# IMD_Fixed.net
KiCad netlist of a schematic drawn in EAGLE
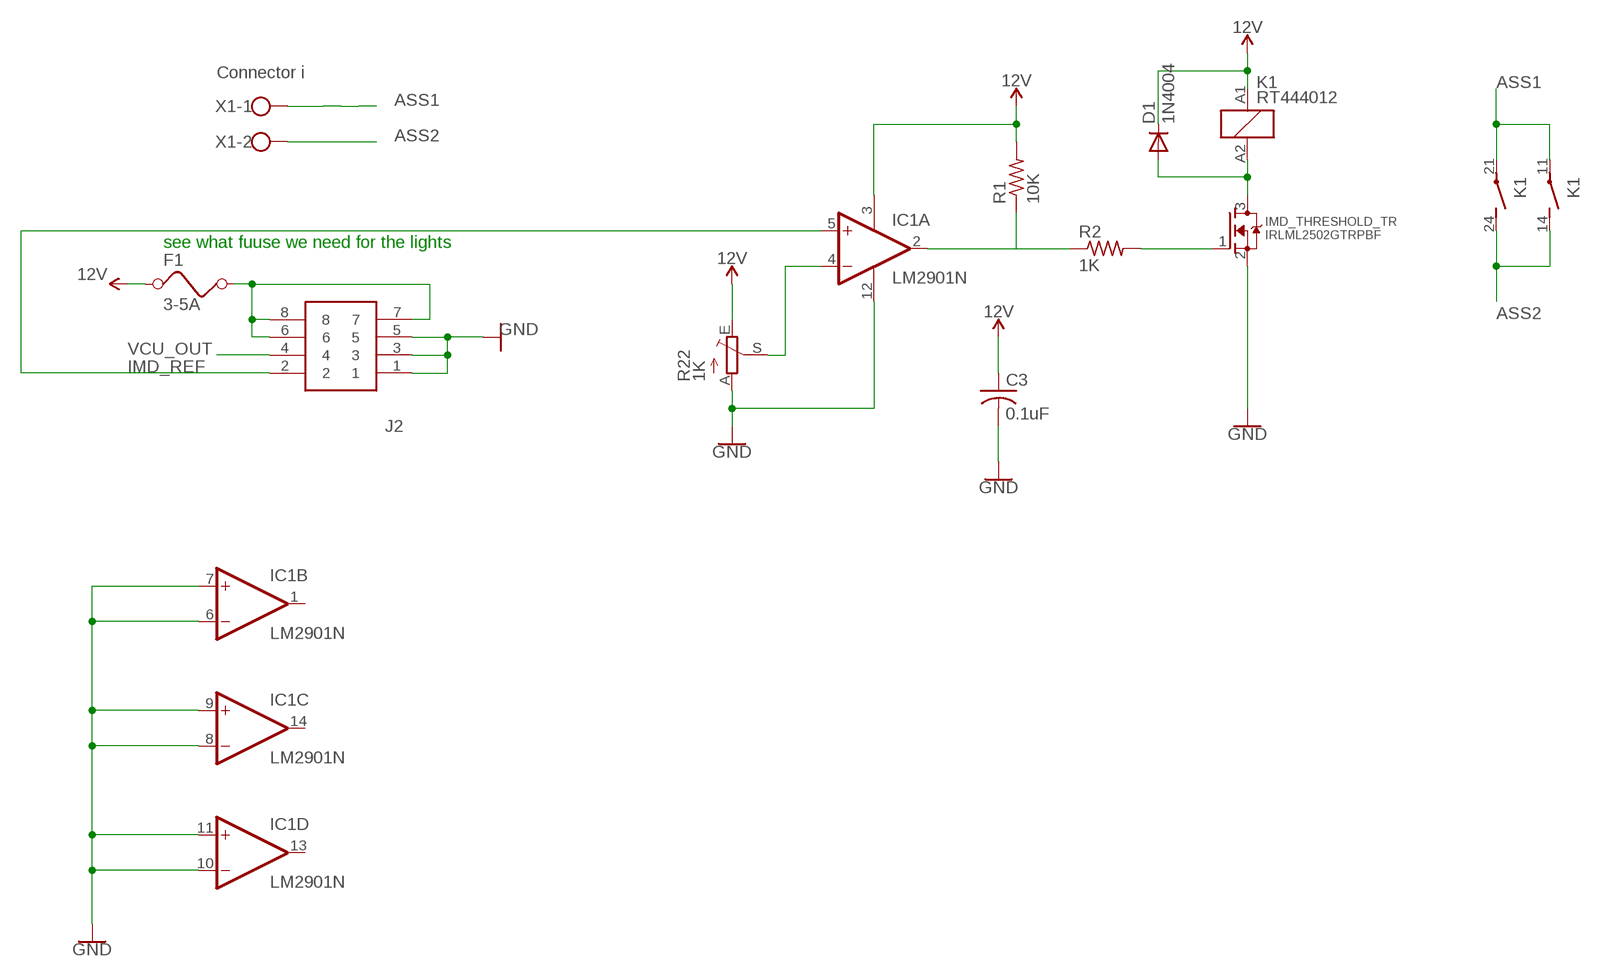
[diagram p0: schematic, sheet 1]
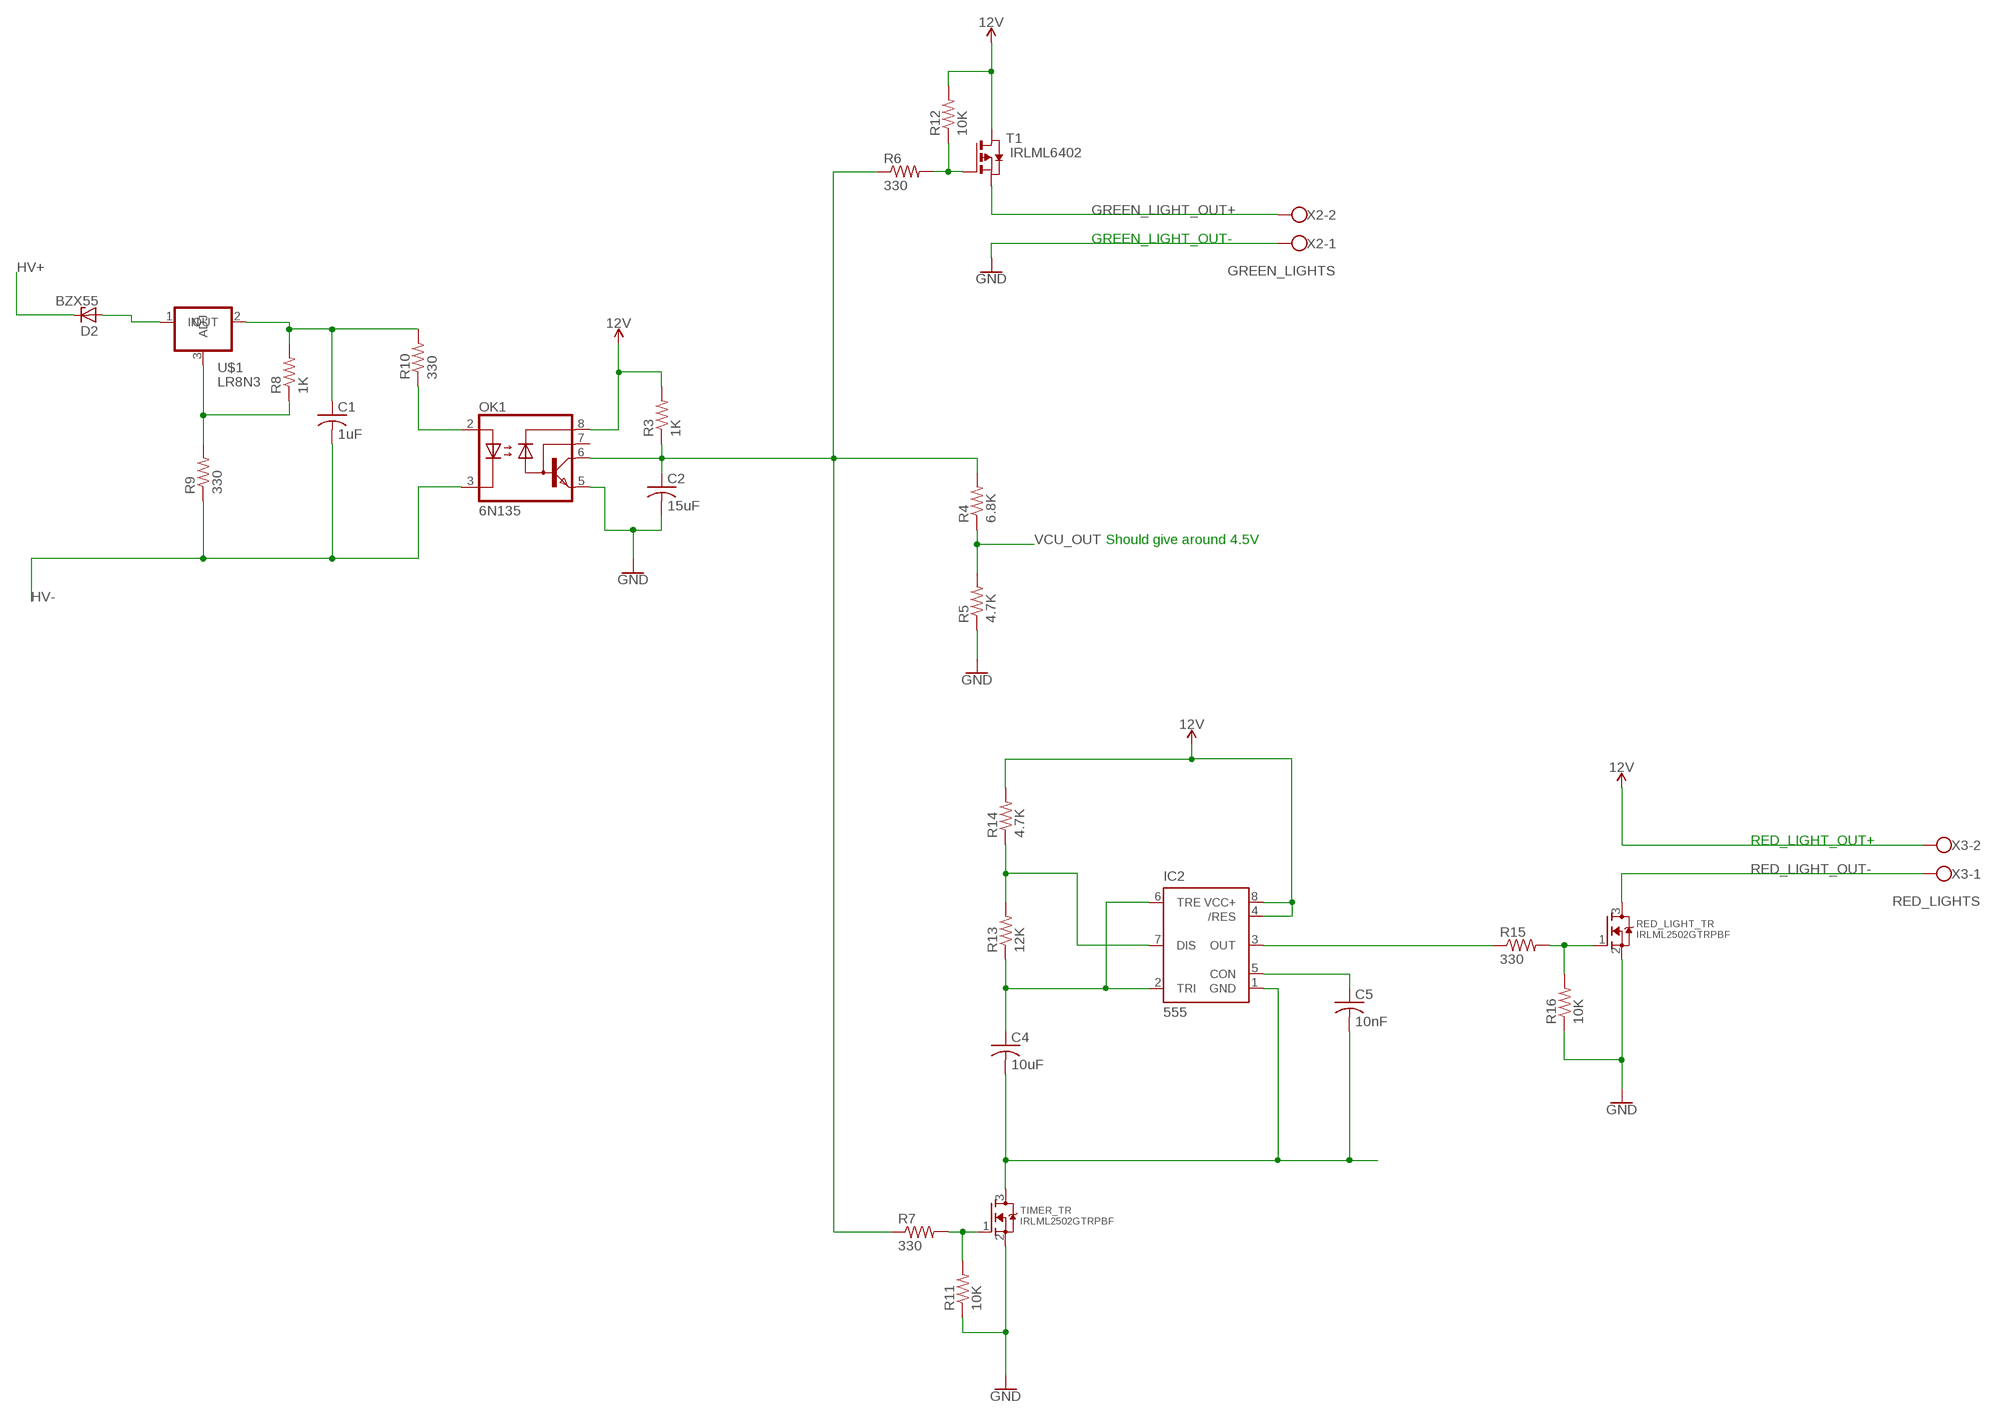
[diagram p1: schematic, sheet 2]

(export (version "E")
  (design (tool "Eeschema 10.0.6"))
  (components
    (comp (ref "C3")
      (value "0.1uF")
      (footprint "eagle-import:C050-024X044")
      (libsource (lib "eagle-import") (part "C-US050-024X044"))
    )
    (comp (ref "D1")
      (value "1N4004")
      (footprint "eagle-import:DO41-10")
      (libsource (lib "eagle-import") (part "1N4004"))
    )
    (comp (ref "F1")
      (value "3-5A")
      (footprint "eagle-import:FUSE")
      (libsource (lib "eagle-import") (part "FUSE"))
    )
    (comp (ref "IC1")
      (value "LM2901N")
      (footprint "eagle-import:DIL14")
      (libsource (lib "eagle-import") (part "LM2901N"))
    )
    (comp (ref "IMD_THRESHOLD_TR")
      (value "IRLML2502GTRPBF")
      (footprint "eagle-import:SOT23")
      (libsource (lib "eagle-import") (part "MOSFET-NREFLOW"))
    )
    (comp (ref "J2")
      (value "T821108A1S100CEU")
      (footprint "eagle-import:HDRV8W64P254_2X4_1778X895X915P")
      (fields (field (name "RS_PART_NUMBER") "1702738"))
      (libsource (lib "eagle-import") (part "T821108A1S100CEU"))
    )
    (comp (ref "K1")
      (value "RT444012")
      (footprint "eagle-import:RT2N_O")
      (libsource (lib "eagle-import") (part "RT44?4012"))
    )
    (comp (ref "R1")
      (value "10K")
      (footprint "eagle-import:R0805")
      (libsource (lib "eagle-import") (part "R-US_R0805"))
    )
    (comp (ref "R2")
      (value "1K")
      (footprint "eagle-import:R0805")
      (libsource (lib "eagle-import") (part "R-US_R0805"))
    )
    (comp (ref "R22")
      (value "1K")
      (footprint "eagle-import:SP19L")
      (libsource (lib "eagle-import") (part "TRIM_EU-B90P"))
    )
    (comp (ref "X1")
      (value "Connector i")
      (footprint "eagle-import:W237-102")
      (fields (field (name "MPN") "237-102"))
      (libsource (lib "eagle-import") (part "W237-102"))
    )
    (comp (ref "C1")
      (value "1uF")
      (footprint "eagle-import:C050-024X044")
      (libsource (lib "eagle-import") (part "C-US050-024X044"))
    )
    (comp (ref "C2")
      (value "15uF")
      (footprint "eagle-import:C050-024X044")
      (libsource (lib "eagle-import") (part "C-US050-024X044"))
    )
    (comp (ref "C4")
      (value "10uF")
      (footprint "eagle-import:C050-024X044")
      (libsource (lib "eagle-import") (part "C-US050-024X044"))
    )
    (comp (ref "C5")
      (value "10nF")
      (footprint "eagle-import:C050-024X044")
      (libsource (lib "eagle-import") (part "C-US050-024X044"))
    )
    (comp (ref "D2")
      (value "BZX55")
      (footprint "eagle-import:DO35Z10")
      (libsource (lib "eagle-import") (part "BZX55"))
    )
    (comp (ref "IC2")
      (value "555")
      (footprint "eagle-import:DIP08-KIT")
      (libsource (lib "eagle-import") (part "555KIT"))
    )
    (comp (ref "OK1")
      (value "6N135")
      (footprint "eagle-import:DIL08")
      (fields (field (name "MF") "FAIRCHILD SEMICONDUCTOR"))
      (libsource (lib "eagle-import") (part "6N135"))
    )
    (comp (ref "R3")
      (value "1K")
      (footprint "eagle-import:M0805")
      (libsource (lib "eagle-import") (part "R-US_M0805"))
    )
    (comp (ref "R4")
      (value "6.8K")
      (footprint "eagle-import:M0805")
      (libsource (lib "eagle-import") (part "R-US_M0805"))
    )
    (comp (ref "R5")
      (value "4.7K")
      (footprint "eagle-import:M0805")
      (libsource (lib "eagle-import") (part "R-US_M0805"))
    )
    (comp (ref "R6")
      (value "330")
      (footprint "eagle-import:M0805")
      (libsource (lib "eagle-import") (part "R-US_M0805"))
    )
    (comp (ref "R7")
      (value "330")
      (footprint "eagle-import:M0805")
      (libsource (lib "eagle-import") (part "R-US_M0805"))
    )
    (comp (ref "R8")
      (value "1K")
      (footprint "eagle-import:0204_7")
      (libsource (lib "eagle-import") (part "R-US_0204/7"))
    )
    (comp (ref "R9")
      (value "330")
      (footprint "eagle-import:0204_7")
      (libsource (lib "eagle-import") (part "R-US_0204/7"))
    )
    (comp (ref "R10")
      (value "330")
      (footprint "eagle-import:0204_7")
      (libsource (lib "eagle-import") (part "R-US_0204/7"))
    )
    (comp (ref "R11")
      (value "10K")
      (footprint "eagle-import:M0805")
      (libsource (lib "eagle-import") (part "R-US_M0805"))
    )
    (comp (ref "R12")
      (value "10K")
      (footprint "eagle-import:M0805")
      (libsource (lib "eagle-import") (part "R-US_M0805"))
    )
    (comp (ref "R13")
      (value "12K")
      (footprint "eagle-import:M0805")
      (libsource (lib "eagle-import") (part "R-US_M0805"))
    )
    (comp (ref "R14")
      (value "4.7K")
      (footprint "eagle-import:M0805")
      (libsource (lib "eagle-import") (part "R-US_M0805"))
    )
    (comp (ref "R15")
      (value "330")
      (footprint "eagle-import:M0805")
      (libsource (lib "eagle-import") (part "R-US_M0805"))
    )
    (comp (ref "R16")
      (value "10K")
      (footprint "eagle-import:M0805")
      (libsource (lib "eagle-import") (part "R-US_M0805"))
    )
    (comp (ref "RED_LIGHT_TR")
      (value "IRLML2502GTRPBF")
      (footprint "eagle-import:SOT23")
      (libsource (lib "eagle-import") (part "MOSFET-NREFLOW"))
    )
    (comp (ref "T1")
      (value "IRLML6402")
      (footprint "eagle-import:SOT-23")
      (libsource (lib "eagle-import") (part "PMOSSOT23"))
    )
    (comp (ref "TIMER_TR")
      (value "IRLML2502GTRPBF")
      (footprint "eagle-import:SOT23")
      (libsource (lib "eagle-import") (part "MOSFET-NREFLOW"))
    )
    (comp (ref "U$1")
      (value "LR8N3")
      (footprint "eagle-import:N3")
      (libsource (lib "eagle-import") (part "N3"))
    )
    (comp (ref "X2")
      (value "GREEN_LIGHTS")
      (footprint "eagle-import:W237-102")
      (fields (field (name "MPN") "237-102"))
      (libsource (lib "eagle-import") (part "W237-102"))
    )
    (comp (ref "X3")
      (value "RED_LIGHTS")
      (footprint "eagle-import:W237-102")
      (fields (field (name "MPN") "237-102"))
      (libsource (lib "eagle-import") (part "W237-102"))
    )
  )
  (nets
    (net (code "1") (name "12V") (class "Default")
      (node (ref "C3") (pin "1") (pinfunction "1_1") (pintype "passive"))
      (node (ref "D1") (pin "C") (pinfunction "C_C") (pintype "passive"))
      (node (ref "F1") (pin "1") (pinfunction "1_1") (pintype "passive"))
      (node (ref "IC1") (pin "3") (pinfunction "V+_3") (pintype "power_in"))
      (node (ref "IC2") (pin "4") (pinfunction "/RES_4") (pintype "input"))
      (node (ref "IC2") (pin "8") (pinfunction "VCC+_8") (pintype "power_in"))
      (node (ref "K1") (pin "A1") (pinfunction "1_A1") (pintype "passive"))
      (node (ref "OK1") (pin "8") (pinfunction "VCC_8") (pintype "passive"))
      (node (ref "R1") (pin "2") (pinfunction "2_2") (pintype "passive"))
      (node (ref "R12") (pin "2") (pinfunction "2_2") (pintype "passive"))
      (node (ref "R14") (pin "2") (pinfunction "2_2") (pintype "passive"))
      (node (ref "R22") (pin "E") (pinfunction "E_E") (pintype "passive"))
      (node (ref "R3") (pin "2") (pinfunction "2_2") (pintype "passive"))
      (node (ref "T1") (pin "1") (pinfunction "D_1") (pintype "passive"))
      (node (ref "X3") (pin "2") (pinfunction "KL_2") (pintype "passive"))
    )
    (net (code "2") (name "ASS1") (class "Default")
      (node (ref "K1") (pin "11") (pinfunction "P_11") (pintype "passive"))
      (node (ref "K1") (pin "21") (pinfunction "P_21") (pintype "passive"))
      (node (ref "X1") (pin "1") (pinfunction "KL_1") (pintype "passive"))
    )
    (net (code "3") (name "ASS2") (class "Default")
      (node (ref "K1") (pin "14") (pinfunction "S_14") (pintype "passive"))
      (node (ref "K1") (pin "24") (pinfunction "S_24") (pintype "passive"))
      (node (ref "X1") (pin "2") (pinfunction "KL_2") (pintype "passive"))
    )
    (net (code "4") (name "GND") (class "Default")
      (node (ref "C2") (pin "2") (pinfunction "2_2") (pintype "passive"))
      (node (ref "C3") (pin "2") (pinfunction "2_2") (pintype "passive"))
      (node (ref "IC1") (pin "10") (pinfunction "-IN_10") (pintype "input"))
      (node (ref "IC1") (pin "11") (pinfunction "+IN_11") (pintype "input"))
      (node (ref "IC1") (pin "12") (pinfunction "V-_12") (pintype "power_in"))
      (node (ref "IC1") (pin "6") (pinfunction "-IN_6") (pintype "input"))
      (node (ref "IC1") (pin "7") (pinfunction "+IN_7") (pintype "input"))
      (node (ref "IC1") (pin "8") (pinfunction "-IN_8") (pintype "input"))
      (node (ref "IC1") (pin "9") (pinfunction "+IN_9") (pintype "input"))
      (node (ref "IMD_THRESHOLD_TR") (pin "2") (pinfunction "S_2") (pintype "bidirectional"))
      (node (ref "J2") (pin "1") (pinfunction "1_1") (pintype "bidirectional"))
      (node (ref "J2") (pin "3") (pinfunction "3_3") (pintype "bidirectional"))
      (node (ref "J2") (pin "5") (pinfunction "5_5") (pintype "bidirectional"))
      (node (ref "OK1") (pin "5") (pinfunction "GND_5") (pintype "passive"))
      (node (ref "R11") (pin "1") (pinfunction "1_1") (pintype "passive"))
      (node (ref "R16") (pin "1") (pinfunction "1_1") (pintype "passive"))
      (node (ref "R22") (pin "A") (pinfunction "A_A") (pintype "passive"))
      (node (ref "R5") (pin "1") (pinfunction "1_1") (pintype "passive"))
      (node (ref "RED_LIGHT_TR") (pin "2") (pinfunction "S_2") (pintype "bidirectional"))
      (node (ref "TIMER_TR") (pin "2") (pinfunction "S_2") (pintype "bidirectional"))
      (node (ref "X2") (pin "1") (pinfunction "KL_1") (pintype "passive"))
    )
    (net (code "5") (name "GREEN_LIGHT_OUT+") (class "Default")
      (node (ref "T1") (pin "2") (pinfunction "S_2") (pintype "passive"))
      (node (ref "X2") (pin "2") (pinfunction "KL_2") (pintype "passive"))
    )
    (net (code "6") (name "HV+") (class "Default")
      (node (ref "D2") (pin "C") (pinfunction "C_C") (pintype "passive"))
    )
    (net (code "7") (name "HV-") (class "Default")
      (node (ref "C1") (pin "2") (pinfunction "2_2") (pintype "passive"))
      (node (ref "OK1") (pin "3") (pinfunction "C_3") (pintype "passive"))
      (node (ref "R9") (pin "1") (pinfunction "1_1") (pintype "passive"))
    )
    (net (code "8") (name "IMD_REF") (class "Default")
      (node (ref "IC1") (pin "5") (pinfunction "+IN_5") (pintype "input"))
      (node (ref "J2") (pin "2") (pinfunction "2_2") (pintype "bidirectional"))
    )
    (net (code "9") (name "Net-(F1-Pad2)") (class "Default")
      (node (ref "F1") (pin "2") (pinfunction "2_2") (pintype "passive"))
      (node (ref "J2") (pin "6") (pinfunction "6_6") (pintype "bidirectional"))
      (node (ref "J2") (pin "7") (pinfunction "7_7") (pintype "bidirectional"))
      (node (ref "J2") (pin "8") (pinfunction "8_8") (pintype "bidirectional"))
    )
    (net (code "10") (name "Net-(IC1A--IN)") (class "Default")
      (node (ref "IC1") (pin "4") (pinfunction "-IN_4") (pintype "input"))
      (node (ref "R22") (pin "S") (pinfunction "S_S") (pintype "passive"))
    )
    (net (code "11") (name "Net-(IC1A-OUT)") (class "Default")
      (node (ref "IC1") (pin "2") (pinfunction "OUT_2") (pintype "output"))
      (node (ref "R1") (pin "1") (pinfunction "1_1") (pintype "passive"))
      (node (ref "R2") (pin "1") (pinfunction "1_1") (pintype "passive"))
    )
    (net (code "12") (name "Net-(IC2-CON)") (class "Default")
      (node (ref "C5") (pin "1") (pinfunction "1_1") (pintype "passive"))
      (node (ref "IC2") (pin "5") (pinfunction "CON_5") (pintype "input"))
    )
    (net (code "13") (name "Net-(IC2-DIS)") (class "Default")
      (node (ref "IC2") (pin "7") (pinfunction "DIS_7") (pintype "input"))
      (node (ref "R13") (pin "2") (pinfunction "2_2") (pintype "passive"))
      (node (ref "R14") (pin "1") (pinfunction "1_1") (pintype "passive"))
    )
    (net (code "14") (name "Net-(IC2-GND)") (class "Default")
      (node (ref "C4") (pin "2") (pinfunction "2_2") (pintype "passive"))
      (node (ref "C5") (pin "2") (pinfunction "2_2") (pintype "passive"))
      (node (ref "IC2") (pin "1") (pinfunction "GND_1") (pintype "power_in"))
      (node (ref "TIMER_TR") (pin "3") (pinfunction "D_3") (pintype "bidirectional"))
    )
    (net (code "15") (name "Net-(IC2-OUT)") (class "Default")
      (node (ref "IC2") (pin "3") (pinfunction "OUT_3") (pintype "output"))
      (node (ref "R15") (pin "1") (pinfunction "1_1") (pintype "passive"))
    )
    (net (code "16") (name "Net-(IC2-TRE)") (class "Default")
      (node (ref "C4") (pin "1") (pinfunction "1_1") (pintype "passive"))
      (node (ref "IC2") (pin "2") (pinfunction "TRI_2") (pintype "input"))
      (node (ref "IC2") (pin "6") (pinfunction "TRE_6") (pintype "input"))
      (node (ref "R13") (pin "1") (pinfunction "1_1") (pintype "passive"))
    )
    (net (code "17") (name "Net-(IMD_THRESHOLD_TR-D)") (class "Default")
      (node (ref "D1") (pin "A") (pinfunction "A_A") (pintype "passive"))
      (node (ref "IMD_THRESHOLD_TR") (pin "3") (pinfunction "D_3") (pintype "bidirectional"))
      (node (ref "K1") (pin "A2") (pinfunction "2_A2") (pintype "passive"))
    )
    (net (code "18") (name "Net-(IMD_THRESHOLD_TR-G)") (class "Default")
      (node (ref "IMD_THRESHOLD_TR") (pin "1") (pinfunction "G_1") (pintype "bidirectional"))
      (node (ref "R2") (pin "2") (pinfunction "2_2") (pintype "passive"))
    )
    (net (code "19") (name "Net-(OK1-A)") (class "Default")
      (node (ref "OK1") (pin "2") (pinfunction "A_2") (pintype "passive"))
      (node (ref "R10") (pin "1") (pinfunction "1_1") (pintype "passive"))
    )
    (net (code "20") (name "Net-(OK1-VO)") (class "Default")
      (node (ref "C2") (pin "1") (pinfunction "1_1") (pintype "passive"))
      (node (ref "OK1") (pin "6") (pinfunction "VO_6") (pintype "passive"))
      (node (ref "R3") (pin "1") (pinfunction "1_1") (pintype "passive"))
      (node (ref "R4") (pin "2") (pinfunction "2_2") (pintype "passive"))
      (node (ref "R6") (pin "1") (pinfunction "1_1") (pintype "passive"))
      (node (ref "R7") (pin "1") (pinfunction "1_1") (pintype "passive"))
    )
    (net (code "21") (name "Net-(RED_LIGHT_TR-G)") (class "Default")
      (node (ref "R15") (pin "2") (pinfunction "2_2") (pintype "passive"))
      (node (ref "R16") (pin "2") (pinfunction "2_2") (pintype "passive"))
      (node (ref "RED_LIGHT_TR") (pin "1") (pinfunction "G_1") (pintype "bidirectional"))
    )
    (net (code "22") (name "Net-(T1-G)") (class "Default")
      (node (ref "R12") (pin "1") (pinfunction "1_1") (pintype "passive"))
      (node (ref "R6") (pin "2") (pinfunction "2_2") (pintype "passive"))
      (node (ref "T1") (pin "3") (pinfunction "G_3") (pintype "passive"))
    )
    (net (code "23") (name "Net-(TIMER_TR-G)") (class "Default")
      (node (ref "R11") (pin "2") (pinfunction "2_2") (pintype "passive"))
      (node (ref "R7") (pin "2") (pinfunction "2_2") (pintype "passive"))
      (node (ref "TIMER_TR") (pin "1") (pinfunction "G_1") (pintype "bidirectional"))
    )
    (net (code "24") (name "Net-(U$1-ADJ)") (class "Default")
      (node (ref "R8") (pin "1") (pinfunction "1_1") (pintype "passive"))
      (node (ref "R9") (pin "2") (pinfunction "2_2") (pintype "passive"))
      (node (ref "U$1") (pin "3") (pinfunction "ADJ_3") (pintype "input"))
    )
    (net (code "25") (name "Net-(U$1-IN)") (class "Default")
      (node (ref "D2") (pin "A") (pinfunction "A_A") (pintype "passive"))
      (node (ref "U$1") (pin "1") (pinfunction "IN_1") (pintype "input"))
    )
    (net (code "26") (name "Net-(U$1-OUT)") (class "Default")
      (node (ref "C1") (pin "1") (pinfunction "1_1") (pintype "passive"))
      (node (ref "R10") (pin "2") (pinfunction "2_2") (pintype "passive"))
      (node (ref "R8") (pin "2") (pinfunction "2_2") (pintype "passive"))
      (node (ref "U$1") (pin "2") (pinfunction "OUT_2") (pintype "output"))
    )
    (net (code "27") (name "RED_LIGHT_OUT-") (class "Default")
      (node (ref "RED_LIGHT_TR") (pin "3") (pinfunction "D_3") (pintype "bidirectional"))
      (node (ref "X3") (pin "1") (pinfunction "KL_1") (pintype "passive"))
    )
    (net (code "28") (name "VCU_OUT") (class "Default")
      (node (ref "J2") (pin "4") (pinfunction "4_4") (pintype "bidirectional"))
      (node (ref "R4") (pin "1") (pinfunction "1_1") (pintype "passive"))
      (node (ref "R5") (pin "2") (pinfunction "2_2") (pintype "passive"))
    )
    (net (code "29") (name "unconnected-(IC1B-OUT-Pad1)") (class "Default")
      (node (ref "IC1") (pin "1") (pinfunction "OUT_1") (pintype "output"))
    )
    (net (code "30") (name "unconnected-(IC1C-OUT-Pad14)") (class "Default")
      (node (ref "IC1") (pin "14") (pinfunction "OUT_14") (pintype "output"))
    )
    (net (code "31") (name "unconnected-(IC1D-OUT-Pad13)") (class "Default")
      (node (ref "IC1") (pin "13") (pinfunction "OUT_13") (pintype "output"))
    )
    (net (code "32") (name "unconnected-(OK1-VB-Pad7)") (class "Default")
      (node (ref "OK1") (pin "7") (pinfunction "VB_7") (pintype "passive"))
    )
  )
)
